# DTB_Brushed_Power_Board_2_0.net
KiCad netlist of a schematic drawn in EAGLE
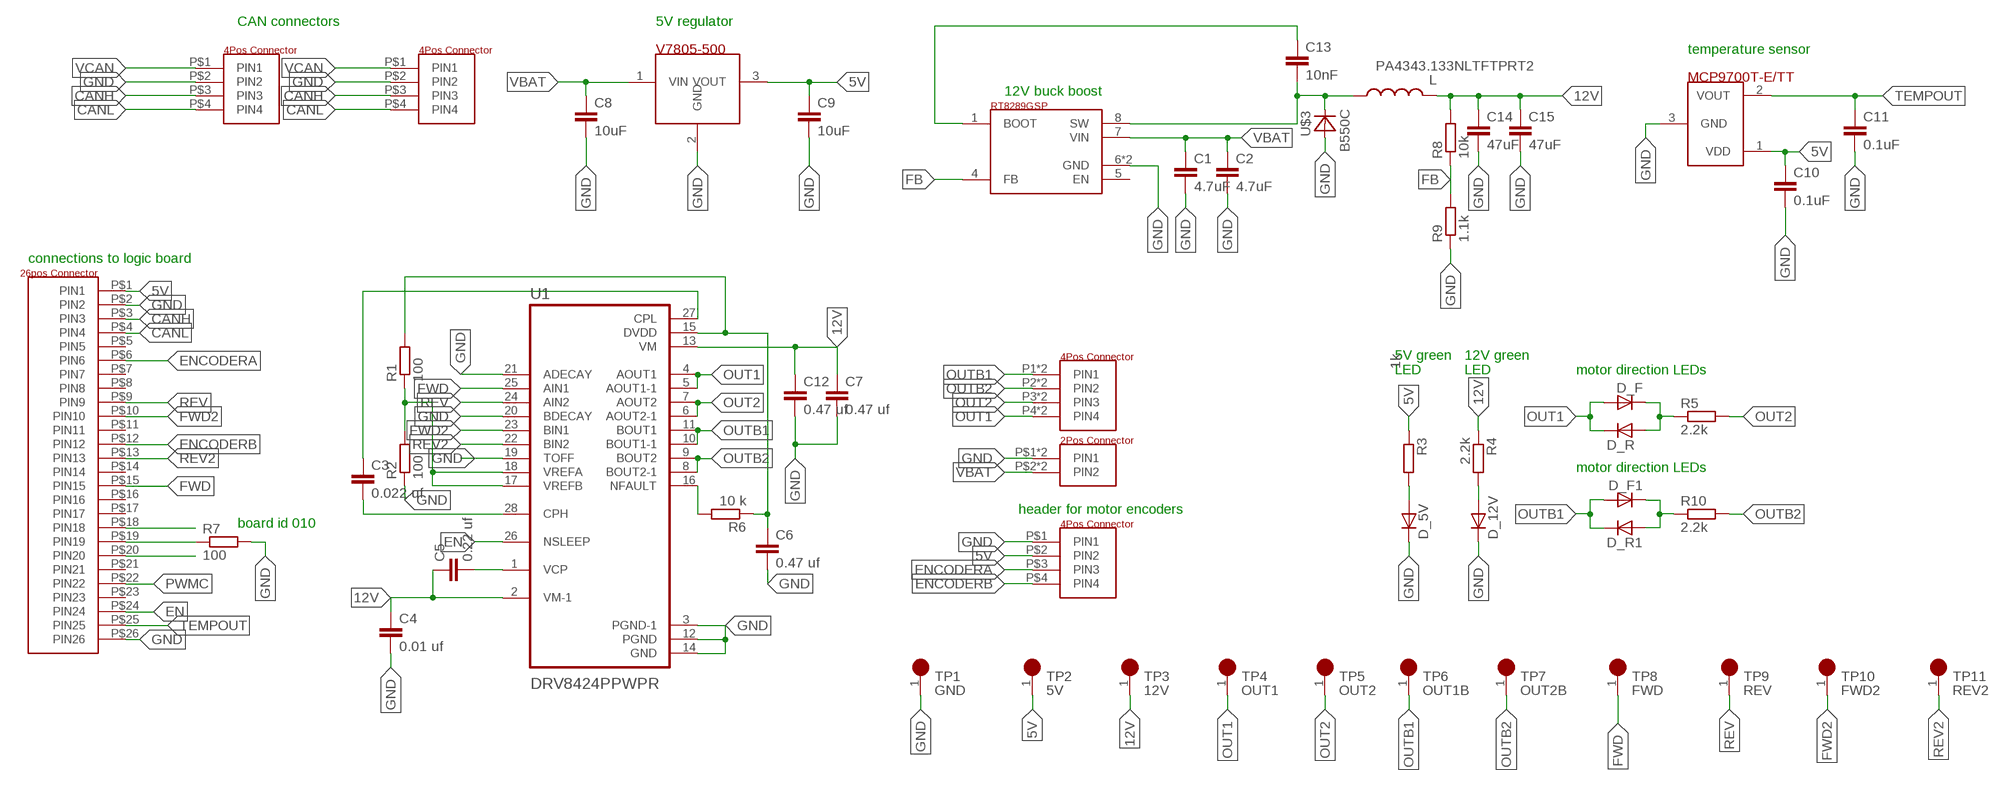
[diagram p0: schematic, sheet 1]

(export (version "E")
  (design (tool "Eeschema 10.0.6"))
  (components
    (comp (ref "C1")
      (value "4.7uF")
      (footprint "eagle-import:C1206")
      (libsource (lib "eagle-import") (part "C-EUC1206"))
    )
    (comp (ref "C2")
      (value "4.7uF")
      (footprint "eagle-import:C1206")
      (libsource (lib "eagle-import") (part "C-EUC1206"))
    )
    (comp (ref "C3")
      (value "0.022 uf")
      (footprint "eagle-import:C1206")
      (libsource (lib "eagle-import") (part "C-EUC1206"))
    )
    (comp (ref "C4")
      (value "0.01 uf")
      (footprint "eagle-import:C1206")
      (libsource (lib "eagle-import") (part "C-EUC1206"))
    )
    (comp (ref "C5")
      (value "0.22 uf")
      (footprint "eagle-import:C1206")
      (libsource (lib "eagle-import") (part "C-EUC1206"))
    )
    (comp (ref "C6")
      (value "0.47 uf")
      (footprint "eagle-import:C1206")
      (libsource (lib "eagle-import") (part "C-EUC1206"))
    )
    (comp (ref "C7")
      (value "0.47 uf")
      (footprint "eagle-import:C1206")
      (libsource (lib "eagle-import") (part "C-EUC1206"))
    )
    (comp (ref "C8")
      (value "10uF")
      (footprint "eagle-import:C1206")
      (libsource (lib "eagle-import") (part "C-EUC1206"))
    )
    (comp (ref "C9")
      (value "10uF")
      (footprint "eagle-import:C1206")
      (libsource (lib "eagle-import") (part "C-EUC1206"))
    )
    (comp (ref "C10")
      (value "0.1uF")
      (footprint "eagle-import:C0603")
      (libsource (lib "eagle-import") (part "C-EUC0603"))
    )
    (comp (ref "C11")
      (value "0.1uF")
      (footprint "eagle-import:C0603")
      (libsource (lib "eagle-import") (part "C-EUC0603"))
    )
    (comp (ref "C12")
      (value "0.47 uf")
      (footprint "eagle-import:C1206")
      (libsource (lib "eagle-import") (part "C-EUC1206"))
    )
    (comp (ref "C13")
      (value "10nF")
      (footprint "eagle-import:C1206")
      (libsource (lib "eagle-import") (part "C-EUC1206"))
    )
    (comp (ref "C14")
      (value "47uF")
      (footprint "eagle-import:C1206")
      (libsource (lib "eagle-import") (part "C-EUC1206"))
    )
    (comp (ref "C15")
      (value "47uF")
      (footprint "eagle-import:C1206")
      (libsource (lib "eagle-import") (part "C-EUC1206"))
    )
    (comp (ref "D_5V")
      (value "LED0603")
      (footprint "eagle-import:DO0603")
      (libsource (lib "eagle-import") (part "LED0603"))
    )
    (comp (ref "D_12V")
      (value "LED0603")
      (footprint "eagle-import:DO0603")
      (libsource (lib "eagle-import") (part "LED0603"))
    )
    (comp (ref "D_F")
      (value "LED0603")
      (footprint "eagle-import:DO0603")
      (libsource (lib "eagle-import") (part "LED0603"))
    )
    (comp (ref "D_F1")
      (value "LED0603")
      (footprint "eagle-import:DO0603")
      (libsource (lib "eagle-import") (part "LED0603"))
    )
    (comp (ref "D_R")
      (value "LED0603")
      (footprint "eagle-import:DO0603")
      (libsource (lib "eagle-import") (part "LED0603"))
    )
    (comp (ref "D_R1")
      (value "LED0603")
      (footprint "eagle-import:DO0603")
      (libsource (lib "eagle-import") (part "LED0603"))
    )
    (comp (ref "L")
      (value "PA4343.133NLTFTPRT2")
      (footprint "eagle-import:INDM140128X650N")
      (libsource (lib "eagle-import") (part "PA4343.133NLTFTPRT2"))
    )
    (comp (ref "R1")
      (value "100")
      (footprint "eagle-import:R0603")
      (libsource (lib "eagle-import") (part "R-EU_R0603"))
    )
    (comp (ref "R2")
      (value "100")
      (footprint "eagle-import:R0603")
      (libsource (lib "eagle-import") (part "R-EU_R0603"))
    )
    (comp (ref "R3")
      (value "1k")
      (footprint "eagle-import:R0603")
      (libsource (lib "eagle-import") (part "R-EU_R0603"))
    )
    (comp (ref "R4")
      (value "2.2k")
      (footprint "eagle-import:R0603")
      (libsource (lib "eagle-import") (part "R-EU_R0603"))
    )
    (comp (ref "R5")
      (value "2.2k")
      (footprint "eagle-import:R0603")
      (libsource (lib "eagle-import") (part "R-EU_R0603"))
    )
    (comp (ref "R6")
      (value "10 k")
      (footprint "eagle-import:R0603")
      (libsource (lib "eagle-import") (part "R-EU_R0603"))
    )
    (comp (ref "R7")
      (value "100")
      (footprint "eagle-import:R0603")
      (libsource (lib "eagle-import") (part "R-EU_R0603"))
    )
    (comp (ref "R8")
      (value "10k")
      (footprint "eagle-import:R0603")
      (libsource (lib "eagle-import") (part "R-EU_R0603"))
    )
    (comp (ref "R9")
      (value "1.1k")
      (footprint "eagle-import:R0603")
      (libsource (lib "eagle-import") (part "R-EU_R0603"))
    )
    (comp (ref "R10")
      (value "2.2k")
      (footprint "eagle-import:R0603")
      (libsource (lib "eagle-import") (part "R-EU_R0603"))
    )
    (comp (ref "TP1")
      (value "GND")
      (footprint "eagle-import:HARWIN_S2751-46R")
      (fields (field (name "MF") "Harwin Inc.") (field (name "MP") "S2751-46R"))
      (libsource (lib "eagle-import") (part "S2751-46R"))
    )
    (comp (ref "TP2")
      (value "5V")
      (footprint "eagle-import:HARWIN_S2751-46R")
      (fields (field (name "MF") "Harwin Inc.") (field (name "MP") "S2751-46R"))
      (libsource (lib "eagle-import") (part "S2751-46R"))
    )
    (comp (ref "TP3")
      (value "12V")
      (footprint "eagle-import:HARWIN_S2751-46R")
      (fields (field (name "MF") "Harwin Inc.") (field (name "MP") "S2751-46R"))
      (libsource (lib "eagle-import") (part "S2751-46R"))
    )
    (comp (ref "TP4")
      (value "OUT1")
      (footprint "eagle-import:HARWIN_S2751-46R")
      (fields (field (name "MF") "Harwin Inc.") (field (name "MP") "S2751-46R"))
      (libsource (lib "eagle-import") (part "S2751-46R"))
    )
    (comp (ref "TP5")
      (value "OUT2")
      (footprint "eagle-import:HARWIN_S2751-46R")
      (fields (field (name "MF") "Harwin Inc.") (field (name "MP") "S2751-46R"))
      (libsource (lib "eagle-import") (part "S2751-46R"))
    )
    (comp (ref "TP6")
      (value "OUT1B")
      (footprint "eagle-import:HARWIN_S2751-46R")
      (fields (field (name "MF") "Harwin Inc.") (field (name "MP") "S2751-46R"))
      (libsource (lib "eagle-import") (part "S2751-46R"))
    )
    (comp (ref "TP7")
      (value "OUT2B")
      (footprint "eagle-import:HARWIN_S2751-46R")
      (fields (field (name "MF") "Harwin Inc.") (field (name "MP") "S2751-46R"))
      (libsource (lib "eagle-import") (part "S2751-46R"))
    )
    (comp (ref "TP8")
      (value "FWD")
      (footprint "eagle-import:HARWIN_S2751-46R")
      (fields (field (name "MF") "Harwin Inc.") (field (name "MP") "S2751-46R"))
      (libsource (lib "eagle-import") (part "S2751-46R"))
    )
    (comp (ref "TP9")
      (value "REV")
      (footprint "eagle-import:HARWIN_S2751-46R")
      (fields (field (name "MF") "Harwin Inc.") (field (name "MP") "S2751-46R"))
      (libsource (lib "eagle-import") (part "S2751-46R"))
    )
    (comp (ref "TP10")
      (value "FWD2")
      (footprint "eagle-import:HARWIN_S2751-46R")
      (fields (field (name "MF") "Harwin Inc.") (field (name "MP") "S2751-46R"))
      (libsource (lib "eagle-import") (part "S2751-46R"))
    )
    (comp (ref "TP11")
      (value "REV2")
      (footprint "eagle-import:HARWIN_S2751-46R")
      (fields (field (name "MF") "Harwin Inc.") (field (name "MP") "S2751-46R"))
      (libsource (lib "eagle-import") (part "S2751-46R"))
    )
    (comp (ref "U$2")
      (value "RT8289GSP")
      (footprint "eagle-import:SO8")
      (libsource (lib "eagle-import") (part "RT8289GSP"))
    )
    (comp (ref "U$3")
      (value "B550C")
      (footprint "eagle-import:SMC")
      (libsource (lib "eagle-import") (part "B550C"))
    )
    (comp (ref "U$4")
      (value "2POS_CONNECTOR,1X2_45A_POWERPOLE")
      (footprint "eagle-import:POWERPOLE_45A_1X2")
      (libsource (lib "eagle-import") (part "2POS_CONNECTOR,1X2_45A_POWERPOLE"))
    )
    (comp (ref "U$6")
      (value "4POS_CONNECTORPOWERPOLE_1X4")
      (footprint "eagle-import:POWERPOLE_45A_1X4")
      (libsource (lib "eagle-import") (part "4POS_CONNECTORPOWERPOLE_1X4"))
    )
    (comp (ref "U$7")
      (value "4POS_CONNECTORMOLEX_MICROFIT3.0_RA_4PIN_2ROW")
      (footprint "eagle-import:MOLEX_MICROFIT3.0_0430450400")
      (libsource (lib "eagle-import") (part "4POS_CONNECTORMOLEX_MICROFIT3.0_RA_4PIN_2ROW"))
    )
    (comp (ref "U$8")
      (value "4POS_CONNECTORMOLEX_MICROFIT3.0_RA_4PIN_2ROW")
      (footprint "eagle-import:MOLEX_MICROFIT3.0_0430450400")
      (libsource (lib "eagle-import") (part "4POS_CONNECTORMOLEX_MICROFIT3.0_RA_4PIN_2ROW"))
    )
    (comp (ref "U$9")
      (value "V7805-500")
      (footprint "eagle-import:SIP3")
      (libsource (lib "eagle-import") (part "V7805-500"))
    )
    (comp (ref "U$10")
      (value "26POS_CONNECTORN2526-6002-RB")
      (footprint "eagle-import:N2526-6002-RB")
      (libsource (lib "eagle-import") (part "26POS_CONNECTORN2526-6002-RB"))
    )
    (comp (ref "U$11")
      (value "MCP9700T-E/TT")
      (footprint "eagle-import:SOT23")
      (libsource (lib "eagle-import") (part "MCP9700T-E/TT"))
    )
    (comp (ref "U$12")
      (value "4POS_CONNECTOR.1\"HEADER")
      (footprint "eagle-import:4POS_HEADER_.1_")
      (libsource (lib "eagle-import") (part "CMR_13347992_4POS_CONNECTOR.1{dblquote}HEADER"))
    )
    (comp (ref "U1")
      (value "DRV8424PPWPR")
      (footprint "eagle-import:IC_TPS61196PWPRQ1")
      (fields (field (name "MF") "Texas Instruments"))
      (libsource (lib "eagle-import") (part "DRV8424PPWPR"))
    )
  )
  (nets
    (net (code "1") (name "5V") (class "Default")
      (node (ref "C10") (pin "1") (pinfunction "1_1") (pintype "passive"))
      (node (ref "C9") (pin "1") (pinfunction "1_1") (pintype "passive"))
      (node (ref "R3") (pin "1") (pinfunction "1_1") (pintype "passive"))
      (node (ref "TP2") (pin "1") (pinfunction "TP_1") (pintype "passive"))
      (node (ref "U$10") (pin "P$1") (pinfunction "PIN1_P$1") (pintype "bidirectional"))
      (node (ref "U$11") (pin "1") (pinfunction "VDD_1") (pintype "bidirectional"))
      (node (ref "U$12") (pin "P$2") (pinfunction "PIN2_P$2") (pintype "bidirectional"))
      (node (ref "U$9") (pin "3") (pinfunction "VOUT_3") (pintype "bidirectional"))
    )
    (net (code "2") (name "12V") (class "Default")
      (node (ref "C12") (pin "1") (pinfunction "1_1") (pintype "passive"))
      (node (ref "C14") (pin "1") (pinfunction "1_1") (pintype "passive"))
      (node (ref "C15") (pin "1") (pinfunction "1_1") (pintype "passive"))
      (node (ref "C4") (pin "1") (pinfunction "1_1") (pintype "passive"))
      (node (ref "C5") (pin "1") (pinfunction "1_1") (pintype "passive"))
      (node (ref "C7") (pin "1") (pinfunction "1_1") (pintype "passive"))
      (node (ref "L") (pin "2") (pinfunction "2_2") (pintype "passive"))
      (node (ref "R4") (pin "1") (pinfunction "1_1") (pintype "passive"))
      (node (ref "R8") (pin "2") (pinfunction "2_2") (pintype "passive"))
      (node (ref "TP3") (pin "1") (pinfunction "TP_1") (pintype "passive"))
      (node (ref "U1") (pin "13") (pinfunction "VM_13") (pintype "power_in"))
      (node (ref "U1") (pin "2") (pinfunction "VM-1_2") (pintype "bidirectional"))
    )
    (net (code "3") (name "CANH") (class "Default")
      (node (ref "U$10") (pin "P$3") (pinfunction "PIN3_P$3") (pintype "bidirectional"))
      (node (ref "U$7") (pin "P$3") (pinfunction "PIN3_P$3") (pintype "bidirectional"))
      (node (ref "U$8") (pin "P$3") (pinfunction "PIN3_P$3") (pintype "bidirectional"))
    )
    (net (code "4") (name "CANL") (class "Default")
      (node (ref "U$10") (pin "P$4") (pinfunction "PIN4_P$4") (pintype "bidirectional"))
      (node (ref "U$7") (pin "P$4") (pinfunction "PIN4_P$4") (pintype "bidirectional"))
      (node (ref "U$8") (pin "P$4") (pinfunction "PIN4_P$4") (pintype "bidirectional"))
    )
    (net (code "5") (name "EN") (class "Default")
      (node (ref "U$10") (pin "P$24") (pinfunction "PIN24_P$24") (pintype "bidirectional"))
      (node (ref "U1") (pin "26") (pinfunction "NSLEEP_26") (pintype "bidirectional"))
    )
    (net (code "6") (name "ENCODERA") (class "Default")
      (node (ref "U$10") (pin "P$6") (pinfunction "PIN6_P$6") (pintype "bidirectional"))
      (node (ref "U$12") (pin "P$3") (pinfunction "PIN3_P$3") (pintype "bidirectional"))
    )
    (net (code "7") (name "ENCODERB") (class "Default")
      (node (ref "U$10") (pin "P$12") (pinfunction "PIN12_P$12") (pintype "bidirectional"))
      (node (ref "U$12") (pin "P$4") (pinfunction "PIN4_P$4") (pintype "bidirectional"))
    )
    (net (code "8") (name "FB") (class "Default")
      (node (ref "R8") (pin "1") (pinfunction "1_1") (pintype "passive"))
      (node (ref "R9") (pin "2") (pinfunction "2_2") (pintype "passive"))
      (node (ref "U$2") (pin "4") (pinfunction "FB_4") (pintype "bidirectional"))
    )
    (net (code "9") (name "FWD") (class "Default")
      (node (ref "TP8") (pin "1") (pinfunction "TP_1") (pintype "passive"))
      (node (ref "U$10") (pin "P$15") (pinfunction "PIN15_P$15") (pintype "bidirectional"))
      (node (ref "U1") (pin "25") (pinfunction "AIN1_25") (pintype "input"))
    )
    (net (code "10") (name "FWD2") (class "Default")
      (node (ref "TP10") (pin "1") (pinfunction "TP_1") (pintype "passive"))
      (node (ref "U$10") (pin "P$10") (pinfunction "PIN10_P$10") (pintype "bidirectional"))
      (node (ref "U1") (pin "23") (pinfunction "BIN1_23") (pintype "input"))
    )
    (net (code "11") (name "GND") (class "Default")
      (node (ref "C1") (pin "2") (pinfunction "2_2") (pintype "passive"))
      (node (ref "C10") (pin "2") (pinfunction "2_2") (pintype "passive"))
      (node (ref "C11") (pin "2") (pinfunction "2_2") (pintype "passive"))
      (node (ref "C12") (pin "2") (pinfunction "2_2") (pintype "passive"))
      (node (ref "C14") (pin "2") (pinfunction "2_2") (pintype "passive"))
      (node (ref "C15") (pin "2") (pinfunction "2_2") (pintype "passive"))
      (node (ref "C2") (pin "2") (pinfunction "2_2") (pintype "passive"))
      (node (ref "C4") (pin "2") (pinfunction "2_2") (pintype "passive"))
      (node (ref "C6") (pin "2") (pinfunction "2_2") (pintype "passive"))
      (node (ref "C7") (pin "2") (pinfunction "2_2") (pintype "passive"))
      (node (ref "C8") (pin "2") (pinfunction "2_2") (pintype "passive"))
      (node (ref "C9") (pin "2") (pinfunction "2_2") (pintype "passive"))
      (node (ref "D_12V") (pin "2") (pinfunction "C_2") (pintype "passive"))
      (node (ref "D_5V") (pin "2") (pinfunction "C_2") (pintype "passive"))
      (node (ref "R2") (pin "1") (pinfunction "1_1") (pintype "passive"))
      (node (ref "R7") (pin "2") (pinfunction "2_2") (pintype "passive"))
      (node (ref "R9") (pin "1") (pinfunction "1_1") (pintype "passive"))
      (node (ref "TP1") (pin "1") (pinfunction "TP_1") (pintype "passive"))
      (node (ref "U$10") (pin "P$2") (pinfunction "PIN2_P$2") (pintype "bidirectional"))
      (node (ref "U$10") (pin "P$26") (pinfunction "PIN26_P$26") (pintype "bidirectional"))
      (node (ref "U$11") (pin "3") (pinfunction "GND_3") (pintype "bidirectional"))
      (node (ref "U$12") (pin "P$1") (pinfunction "PIN1_P$1") (pintype "bidirectional"))
      (node (ref "U$2") (pin "6") (pinfunction "GND_6") (pintype "bidirectional"))
      (node (ref "U$2") (pin "GND,EXPOSEDPAD") (pinfunction "GND_GND,EXPOSEDPAD") (pintype "bidirectional"))
      (node (ref "U$3") (pin "A") (pinfunction "A_A") (pintype "passive"))
      (node (ref "U$4") (pin "P$1") (pinfunction "PIN1_P$1") (pintype "bidirectional"))
      (node (ref "U$4") (pin "P$5") (pinfunction "PIN1_P$5") (pintype "bidirectional"))
      (node (ref "U$7") (pin "P$2") (pinfunction "PIN2_P$2") (pintype "bidirectional"))
      (node (ref "U$8") (pin "P$2") (pinfunction "PIN2_P$2") (pintype "bidirectional"))
      (node (ref "U$9") (pin "2") (pinfunction "GND_2") (pintype "bidirectional"))
      (node (ref "U1") (pin "12") (pinfunction "PGND_12") (pintype "power_in"))
      (node (ref "U1") (pin "14") (pinfunction "GND_14") (pintype "power_in"))
      (node (ref "U1") (pin "19") (pinfunction "TOFF_19") (pintype "input"))
      (node (ref "U1") (pin "20") (pinfunction "BDECAY_20") (pintype "input"))
      (node (ref "U1") (pin "21") (pinfunction "ADECAY_21") (pintype "input"))
      (node (ref "U1") (pin "3") (pinfunction "PGND-1_3") (pintype "power_in"))
    )
    (net (code "12") (name "Net-(D_5V-A)") (class "Default")
      (node (ref "D_5V") (pin "1") (pinfunction "A_1") (pintype "passive"))
      (node (ref "R3") (pin "2") (pinfunction "2_2") (pintype "passive"))
    )
    (net (code "13") (name "Net-(D_12V-A)") (class "Default")
      (node (ref "D_12V") (pin "1") (pinfunction "A_1") (pintype "passive"))
      (node (ref "R4") (pin "2") (pinfunction "2_2") (pintype "passive"))
    )
    (net (code "14") (name "Net-(D_F-C)") (class "Default")
      (node (ref "D_F") (pin "2") (pinfunction "C_2") (pintype "passive"))
      (node (ref "D_R") (pin "1") (pinfunction "A_1") (pintype "passive"))
      (node (ref "R5") (pin "1") (pinfunction "1_1") (pintype "passive"))
    )
    (net (code "15") (name "Net-(D_F1-C)") (class "Default")
      (node (ref "D_F1") (pin "2") (pinfunction "C_2") (pintype "passive"))
      (node (ref "D_R1") (pin "1") (pinfunction "A_1") (pintype "passive"))
      (node (ref "R10") (pin "1") (pinfunction "1_1") (pintype "passive"))
    )
    (net (code "16") (name "Net-(U$2-BOOT)") (class "Default")
      (node (ref "C13") (pin "1") (pinfunction "1_1") (pintype "passive"))
      (node (ref "U$2") (pin "1") (pinfunction "BOOT_1") (pintype "bidirectional"))
    )
    (net (code "17") (name "Net-(U$2-SW)") (class "Default")
      (node (ref "C13") (pin "2") (pinfunction "2_2") (pintype "passive"))
      (node (ref "L") (pin "1") (pinfunction "1_1") (pintype "passive"))
      (node (ref "U$2") (pin "8") (pinfunction "SW_8") (pintype "bidirectional"))
      (node (ref "U$3") (pin "C") (pinfunction "C_C") (pintype "passive"))
    )
    (net (code "18") (name "Net-(U$10-PIN19)") (class "Default")
      (node (ref "R7") (pin "1") (pinfunction "1_1") (pintype "passive"))
      (node (ref "U$10") (pin "P$19") (pinfunction "PIN19_P$19") (pintype "bidirectional"))
    )
    (net (code "19") (name "Net-(U1-CPH)") (class "Default")
      (node (ref "C3") (pin "2") (pinfunction "2_2") (pintype "passive"))
      (node (ref "U1") (pin "28") (pinfunction "CPH_28") (pintype "bidirectional"))
    )
    (net (code "20") (name "Net-(U1-CPL)") (class "Default")
      (node (ref "C3") (pin "1") (pinfunction "1_1") (pintype "passive"))
      (node (ref "U1") (pin "27") (pinfunction "CPL_27") (pintype "power_in"))
    )
    (net (code "21") (name "Net-(U1-DVDD)") (class "Default")
      (node (ref "C6") (pin "1") (pinfunction "1_1") (pintype "passive"))
      (node (ref "R1") (pin "2") (pinfunction "2_2") (pintype "passive"))
      (node (ref "R6") (pin "1") (pinfunction "1_1") (pintype "passive"))
      (node (ref "U1") (pin "15") (pinfunction "DVDD_15") (pintype "power_in"))
    )
    (net (code "22") (name "Net-(U1-NFAULT)") (class "Default")
      (node (ref "R6") (pin "2") (pinfunction "2_2") (pintype "passive"))
      (node (ref "U1") (pin "16") (pinfunction "NFAULT_16") (pintype "output"))
    )
    (net (code "23") (name "Net-(U1-VCP)") (class "Default")
      (node (ref "C5") (pin "2") (pinfunction "2_2") (pintype "passive"))
      (node (ref "U1") (pin "1") (pinfunction "VCP_1") (pintype "bidirectional"))
    )
    (net (code "24") (name "Net-(U1-VREFA)") (class "Default")
      (node (ref "R1") (pin "1") (pinfunction "1_1") (pintype "passive"))
      (node (ref "R2") (pin "2") (pinfunction "2_2") (pintype "passive"))
      (node (ref "U1") (pin "17") (pinfunction "VREFB_17") (pintype "input"))
      (node (ref "U1") (pin "18") (pinfunction "VREFA_18") (pintype "input"))
    )
    (net (code "25") (name "OUT1") (class "Default")
      (node (ref "D_F") (pin "1") (pinfunction "A_1") (pintype "passive"))
      (node (ref "D_R") (pin "2") (pinfunction "C_2") (pintype "passive"))
      (node (ref "TP4") (pin "1") (pinfunction "TP_1") (pintype "passive"))
      (node (ref "U$6") (pin "P4") (pinfunction "PIN4_P4") (pintype "bidirectional"))
      (node (ref "U$6") (pin "P4B") (pinfunction "PIN4_P4B") (pintype "bidirectional"))
      (node (ref "U1") (pin "4") (pinfunction "AOUT1_4") (pintype "output"))
      (node (ref "U1") (pin "5") (pinfunction "AOUT1-1_5") (pintype "output"))
    )
    (net (code "26") (name "OUT2") (class "Default")
      (node (ref "R5") (pin "2") (pinfunction "2_2") (pintype "passive"))
      (node (ref "TP5") (pin "1") (pinfunction "TP_1") (pintype "passive"))
      (node (ref "U$6") (pin "P3") (pinfunction "PIN3_P3") (pintype "bidirectional"))
      (node (ref "U$6") (pin "P3B") (pinfunction "PIN3_P3B") (pintype "bidirectional"))
      (node (ref "U1") (pin "6") (pinfunction "AOUT2-1_6") (pintype "output"))
      (node (ref "U1") (pin "7") (pinfunction "AOUT2_7") (pintype "output"))
    )
    (net (code "27") (name "OUTB1") (class "Default")
      (node (ref "D_F1") (pin "1") (pinfunction "A_1") (pintype "passive"))
      (node (ref "D_R1") (pin "2") (pinfunction "C_2") (pintype "passive"))
      (node (ref "TP6") (pin "1") (pinfunction "TP_1") (pintype "passive"))
      (node (ref "U$6") (pin "P1") (pinfunction "PIN1_P1") (pintype "bidirectional"))
      (node (ref "U$6") (pin "P1B") (pinfunction "PIN1_P1B") (pintype "bidirectional"))
      (node (ref "U1") (pin "10") (pinfunction "BOUT1-1_10") (pintype "output"))
      (node (ref "U1") (pin "11") (pinfunction "BOUT1_11") (pintype "output"))
    )
    (net (code "28") (name "OUTB2") (class "Default")
      (node (ref "R10") (pin "2") (pinfunction "2_2") (pintype "passive"))
      (node (ref "TP7") (pin "1") (pinfunction "TP_1") (pintype "passive"))
      (node (ref "U$6") (pin "P2") (pinfunction "PIN2_P2") (pintype "bidirectional"))
      (node (ref "U$6") (pin "P2B") (pinfunction "PIN2_P2B") (pintype "bidirectional"))
      (node (ref "U1") (pin "8") (pinfunction "BOUT2-1_8") (pintype "output"))
      (node (ref "U1") (pin "9") (pinfunction "BOUT2_9") (pintype "output"))
    )
    (net (code "29") (name "PWMC") (class "Default")
      (node (ref "U$10") (pin "P$22") (pinfunction "PIN22_P$22") (pintype "bidirectional"))
    )
    (net (code "30") (name "REV") (class "Default")
      (node (ref "TP9") (pin "1") (pinfunction "TP_1") (pintype "passive"))
      (node (ref "U$10") (pin "P$9") (pinfunction "PIN9_P$9") (pintype "bidirectional"))
      (node (ref "U1") (pin "24") (pinfunction "AIN2_24") (pintype "input"))
    )
    (net (code "31") (name "REV2") (class "Default")
      (node (ref "TP11") (pin "1") (pinfunction "TP_1") (pintype "passive"))
      (node (ref "U$10") (pin "P$13") (pinfunction "PIN13_P$13") (pintype "bidirectional"))
      (node (ref "U1") (pin "22") (pinfunction "BIN2_22") (pintype "input"))
    )
    (net (code "32") (name "TEMPOUT") (class "Default")
      (node (ref "C11") (pin "1") (pinfunction "1_1") (pintype "passive"))
      (node (ref "U$10") (pin "P$25") (pinfunction "PIN25_P$25") (pintype "bidirectional"))
      (node (ref "U$11") (pin "2") (pinfunction "VOUT_2") (pintype "bidirectional"))
    )
    (net (code "33") (name "VBAT") (class "Default")
      (node (ref "C1") (pin "1") (pinfunction "1_1") (pintype "passive"))
      (node (ref "C2") (pin "1") (pinfunction "1_1") (pintype "passive"))
      (node (ref "C8") (pin "1") (pinfunction "1_1") (pintype "passive"))
      (node (ref "U$2") (pin "7") (pinfunction "VIN_7") (pintype "bidirectional"))
      (node (ref "U$4") (pin "P$2") (pinfunction "PIN2_P$2") (pintype "bidirectional"))
      (node (ref "U$4") (pin "P$6") (pinfunction "PIN2_P$6") (pintype "bidirectional"))
      (node (ref "U$9") (pin "1") (pinfunction "VIN_1") (pintype "bidirectional"))
    )
    (net (code "34") (name "VCAN") (class "Default")
      (node (ref "U$7") (pin "P$1") (pinfunction "PIN1_P$1") (pintype "bidirectional"))
      (node (ref "U$8") (pin "P$1") (pinfunction "PIN1_P$1") (pintype "bidirectional"))
    )
    (net (code "35") (name "unconnected-(U$2-EN-Pad5)") (class "Default")
      (node (ref "U$2") (pin "5") (pinfunction "EN_5") (pintype "bidirectional"))
    )
    (net (code "36") (name "unconnected-(U$10-PIN5-PadP$5)") (class "Default")
      (node (ref "U$10") (pin "P$5") (pinfunction "PIN5_P$5") (pintype "bidirectional"))
    )
    (net (code "37") (name "unconnected-(U$10-PIN7-PadP$7)") (class "Default")
      (node (ref "U$10") (pin "P$7") (pinfunction "PIN7_P$7") (pintype "bidirectional"))
    )
    (net (code "38") (name "unconnected-(U$10-PIN8-PadP$8)") (class "Default")
      (node (ref "U$10") (pin "P$8") (pinfunction "PIN8_P$8") (pintype "bidirectional"))
    )
    (net (code "39") (name "unconnected-(U$10-PIN11-PadP$11)") (class "Default")
      (node (ref "U$10") (pin "P$11") (pinfunction "PIN11_P$11") (pintype "bidirectional"))
    )
    (net (code "40") (name "unconnected-(U$10-PIN14-PadP$14)") (class "Default")
      (node (ref "U$10") (pin "P$14") (pinfunction "PIN14_P$14") (pintype "bidirectional"))
    )
    (net (code "41") (name "unconnected-(U$10-PIN16-PadP$16)") (class "Default")
      (node (ref "U$10") (pin "P$16") (pinfunction "PIN16_P$16") (pintype "bidirectional"))
    )
    (net (code "42") (name "unconnected-(U$10-PIN17-PadP$17)") (class "Default")
      (node (ref "U$10") (pin "P$17") (pinfunction "PIN17_P$17") (pintype "bidirectional"))
    )
    (net (code "43") (name "unconnected-(U$10-PIN18-PadP$18)") (class "Default")
      (node (ref "U$10") (pin "P$18") (pinfunction "PIN18_P$18") (pintype "bidirectional"))
    )
    (net (code "44") (name "unconnected-(U$10-PIN20-PadP$20)") (class "Default")
      (node (ref "U$10") (pin "P$20") (pinfunction "PIN20_P$20") (pintype "bidirectional"))
    )
    (net (code "45") (name "unconnected-(U$10-PIN21-PadP$21)") (class "Default")
      (node (ref "U$10") (pin "P$21") (pinfunction "PIN21_P$21") (pintype "bidirectional"))
    )
    (net (code "46") (name "unconnected-(U$10-PIN23-PadP$23)") (class "Default")
      (node (ref "U$10") (pin "P$23") (pinfunction "PIN23_P$23") (pintype "bidirectional"))
    )
  )
)
